# imu-adapter-e407.net
KiCad netlist of a schematic drawn in EAGLE
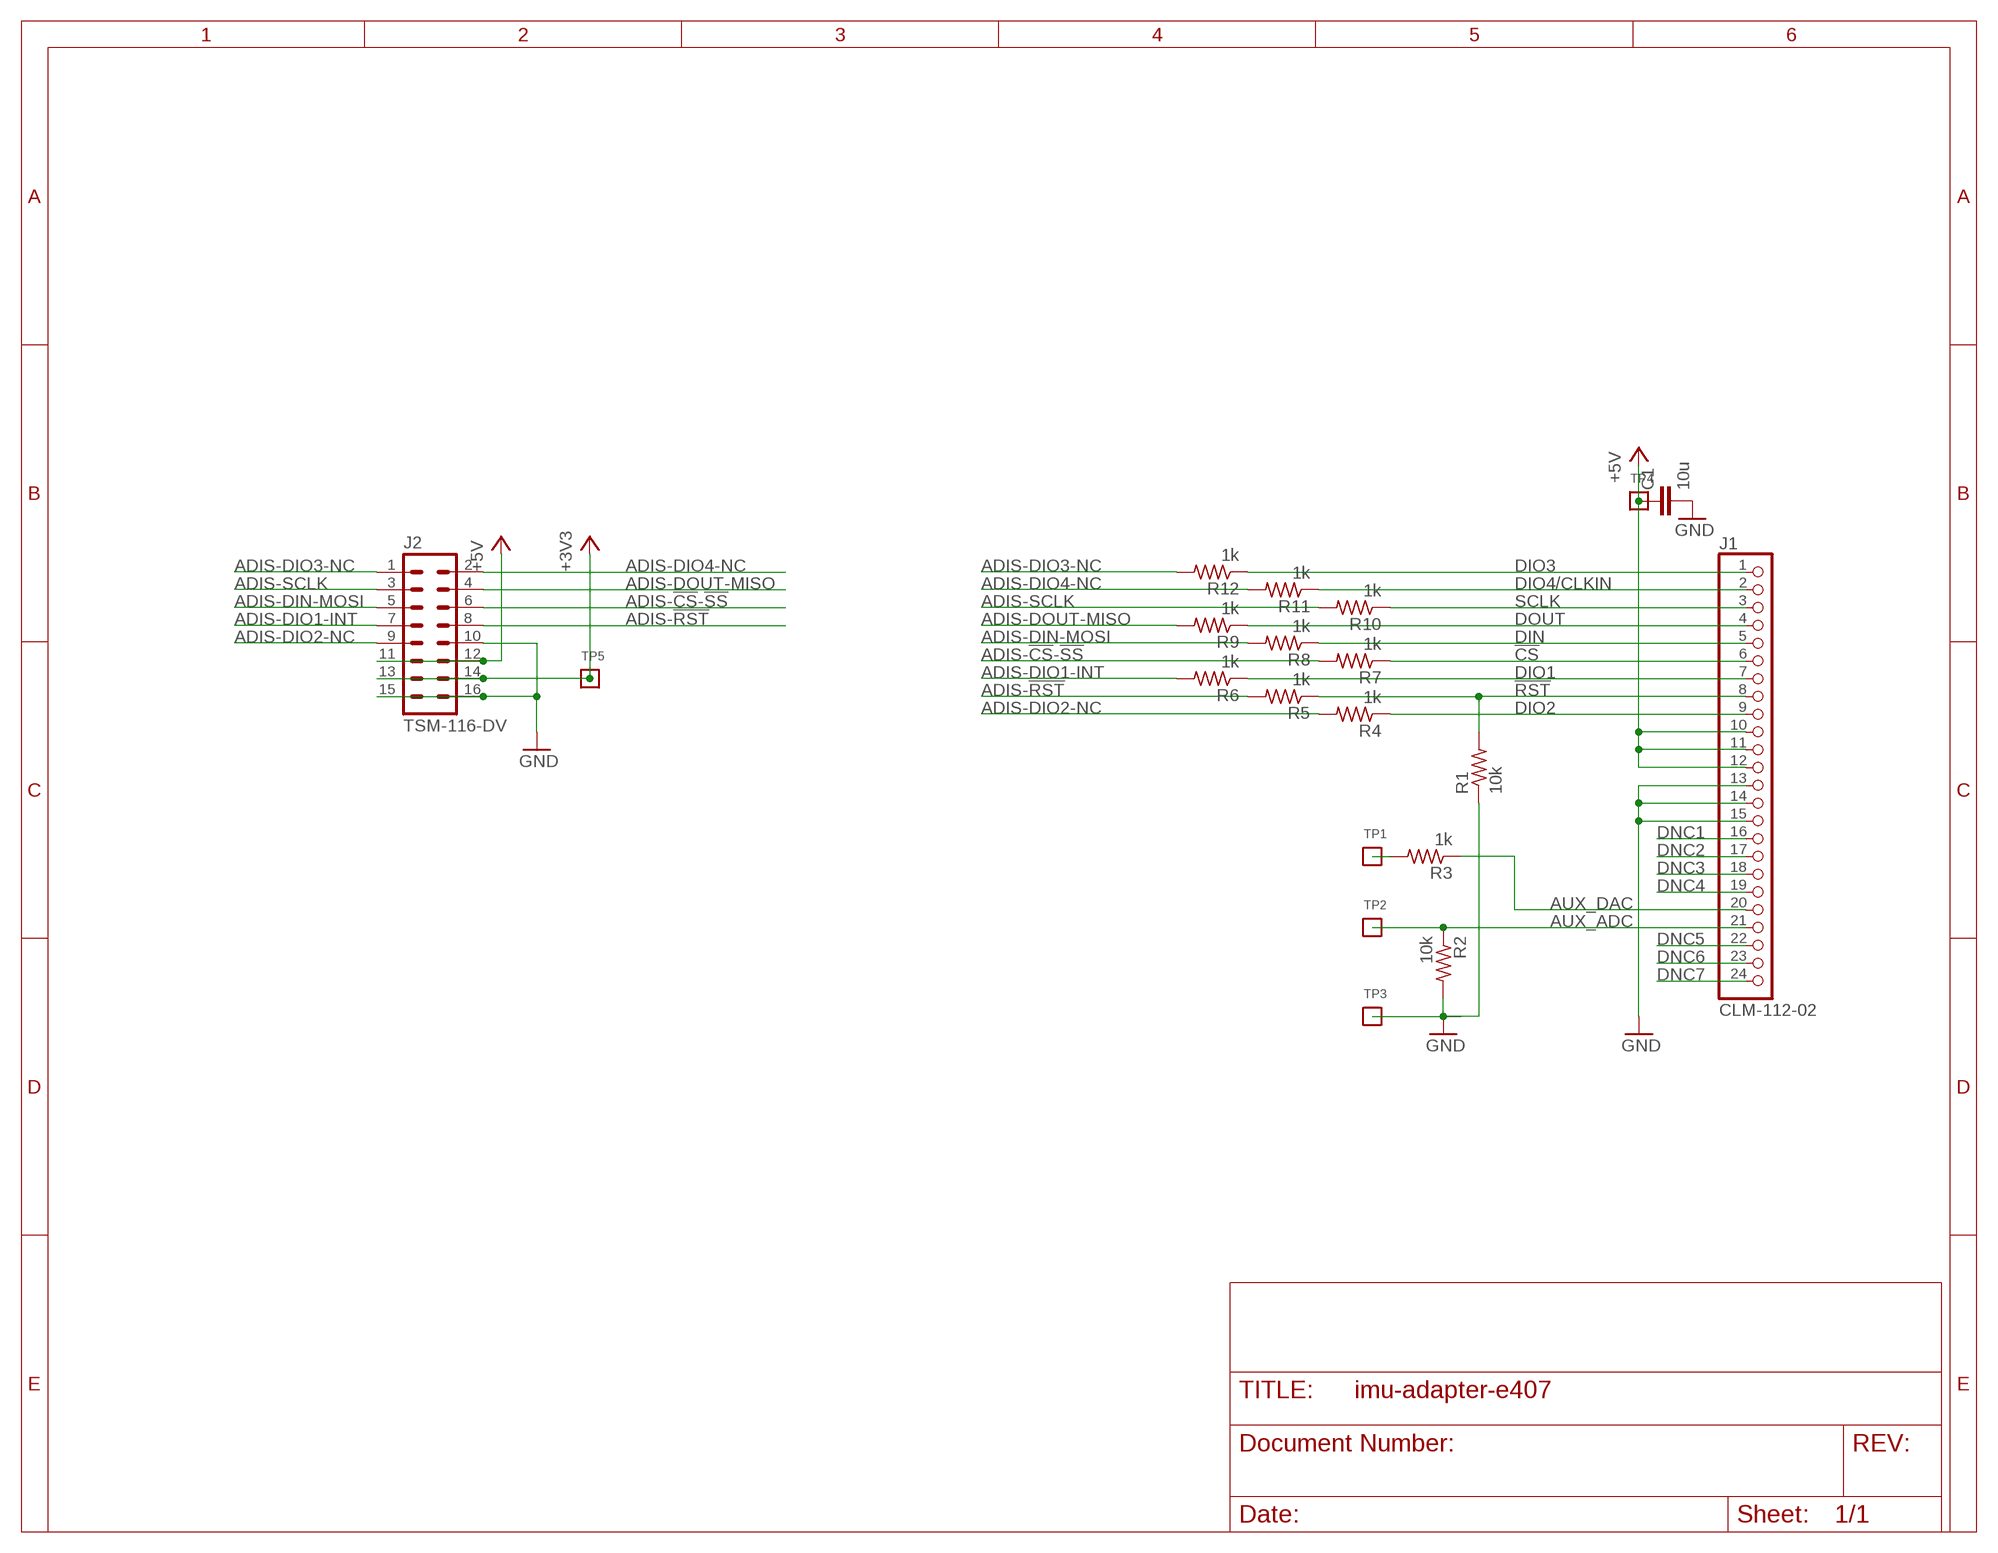
[diagram p0: schematic, sheet 1]

(export (version "E")
  (design (tool "Eeschema 10.0.6"))
  (components
    (comp (ref "C1")
      (value "10u")
      (footprint "eagle-import:0805-B-NOSILK")
      (libsource (lib "eagle-import") (part "C-EU0805-B-NOSILK"))
    )
    (comp (ref "J1")
      (value "CLM-112-02")
      (footprint "eagle-import:CLM-112-02-XX-D-A")
      (libsource (lib "eagle-import") (part "CLM-112-02"))
    )
    (comp (ref "J2")
      (value "TSM-116-DV")
      (footprint "eagle-import:TSM-116-DV")
      (libsource (lib "eagle-import") (part "TSM-116-DV"))
    )
    (comp (ref "R1")
      (value "10k")
      (footprint "eagle-import:0603-B-NOSILK")
      (libsource (lib "eagle-import") (part "R-US_0603-B-NOSILK"))
    )
    (comp (ref "R2")
      (value "10k")
      (footprint "eagle-import:0603-B-NOSILK")
      (libsource (lib "eagle-import") (part "R-US_0603-B-NOSILK"))
    )
    (comp (ref "R3")
      (value "1k")
      (footprint "eagle-import:0603-B-NOSILK")
      (libsource (lib "eagle-import") (part "R-US_0603-B-NOSILK"))
    )
    (comp (ref "R4")
      (value "1k")
      (footprint "eagle-import:0603-B-NOSILK")
      (libsource (lib "eagle-import") (part "R-US_0603-B-NOSILK"))
    )
    (comp (ref "R5")
      (value "1k")
      (footprint "eagle-import:0603-B-NOSILK")
      (libsource (lib "eagle-import") (part "R-US_0603-B-NOSILK"))
    )
    (comp (ref "R6")
      (value "1k")
      (footprint "eagle-import:0603-B-NOSILK")
      (libsource (lib "eagle-import") (part "R-US_0603-B-NOSILK"))
    )
    (comp (ref "R7")
      (value "1k")
      (footprint "eagle-import:0603-B-NOSILK")
      (libsource (lib "eagle-import") (part "R-US_0603-B-NOSILK"))
    )
    (comp (ref "R8")
      (value "1k")
      (footprint "eagle-import:0603-B-NOSILK")
      (libsource (lib "eagle-import") (part "R-US_0603-B-NOSILK"))
    )
    (comp (ref "R9")
      (value "1k")
      (footprint "eagle-import:0603-B-NOSILK")
      (libsource (lib "eagle-import") (part "R-US_0603-B-NOSILK"))
    )
    (comp (ref "R10")
      (value "1k")
      (footprint "eagle-import:0603-B-NOSILK")
      (libsource (lib "eagle-import") (part "R-US_0603-B-NOSILK"))
    )
    (comp (ref "R11")
      (value "1k")
      (footprint "eagle-import:0603-B-NOSILK")
      (libsource (lib "eagle-import") (part "R-US_0603-B-NOSILK"))
    )
    (comp (ref "R12")
      (value "1k")
      (footprint "eagle-import:0603-B-NOSILK")
      (libsource (lib "eagle-import") (part "R-US_0603-B-NOSILK"))
    )
    (comp (ref "TP1")
      (value "TEST-POINT")
      (footprint "eagle-import:2MM-TEST-POINT")
      (libsource (lib "eagle-import") (part "TEST-POINT"))
    )
    (comp (ref "TP2")
      (value "TEST-POINT")
      (footprint "eagle-import:2MM-TEST-POINT")
      (libsource (lib "eagle-import") (part "TEST-POINT"))
    )
    (comp (ref "TP3")
      (value "TEST-POINT")
      (footprint "eagle-import:2MM-TEST-POINT")
      (libsource (lib "eagle-import") (part "TEST-POINT"))
    )
    (comp (ref "TP4")
      (value "TEST-POINT")
      (footprint "eagle-import:2MM-TEST-POINT")
      (libsource (lib "eagle-import") (part "TEST-POINT"))
    )
    (comp (ref "TP5")
      (value "TEST-POINT")
      (footprint "eagle-import:2MM-TEST-POINT")
      (libsource (lib "eagle-import") (part "TEST-POINT"))
    )
  )
  (nets
    (net (code "1") (name "+3V3") (class "Default")
      (node (ref "J2") (pin "13") (pinfunction "13_13") (pintype "passive"))
      (node (ref "J2") (pin "14") (pinfunction "14_14") (pintype "passive"))
      (node (ref "TP5") (pin "1") (pinfunction "P$1_1") (pintype "passive"))
    )
    (net (code "2") (name "+5V") (class "Default")
      (node (ref "C1") (pin "1") (pinfunction "1_1") (pintype "passive"))
      (node (ref "J1") (pin "10") (pinfunction "10_10") (pintype "passive"))
      (node (ref "J1") (pin "11") (pinfunction "11_11") (pintype "passive"))
      (node (ref "J1") (pin "12") (pinfunction "12_12") (pintype "passive"))
      (node (ref "J2") (pin "11") (pinfunction "11_11") (pintype "passive"))
      (node (ref "J2") (pin "12") (pinfunction "12_12") (pintype "passive"))
      (node (ref "TP4") (pin "1") (pinfunction "P$1_1") (pintype "passive"))
    )
    (net (code "3") (name "/ADIS-DIN-MOSI") (class "Default")
      (node (ref "J2") (pin "5") (pinfunction "5_5") (pintype "passive"))
      (node (ref "R8") (pin "2") (pinfunction "2_2") (pintype "passive"))
    )
    (net (code "4") (name "/ADIS-DIO1-INT") (class "Default")
      (node (ref "J2") (pin "7") (pinfunction "7_7") (pintype "passive"))
      (node (ref "R6") (pin "2") (pinfunction "2_2") (pintype "passive"))
    )
    (net (code "5") (name "/ADIS-DIO2-NC") (class "Default")
      (node (ref "J2") (pin "9") (pinfunction "9_9") (pintype "passive"))
      (node (ref "R4") (pin "2") (pinfunction "2_2") (pintype "passive"))
    )
    (net (code "6") (name "/ADIS-DIO3-NC") (class "Default")
      (node (ref "J2") (pin "1") (pinfunction "1_1") (pintype "passive"))
      (node (ref "R12") (pin "2") (pinfunction "2_2") (pintype "passive"))
    )
    (net (code "7") (name "/ADIS-DIO4-NC") (class "Default")
      (node (ref "J2") (pin "2") (pinfunction "2_2") (pintype "passive"))
      (node (ref "R11") (pin "2") (pinfunction "2_2") (pintype "passive"))
    )
    (net (code "8") (name "/ADIS-DOUT-MISO") (class "Default")
      (node (ref "J2") (pin "4") (pinfunction "4_4") (pintype "passive"))
      (node (ref "R9") (pin "2") (pinfunction "2_2") (pintype "passive"))
    )
    (net (code "9") (name "/ADIS-SCLK") (class "Default")
      (node (ref "J2") (pin "3") (pinfunction "3_3") (pintype "passive"))
      (node (ref "R10") (pin "2") (pinfunction "2_2") (pintype "passive"))
    )
    (net (code "10") (name "/ADIS-~{CS}-~{SS}") (class "Default")
      (node (ref "J2") (pin "6") (pinfunction "6_6") (pintype "passive"))
      (node (ref "R7") (pin "2") (pinfunction "2_2") (pintype "passive"))
    )
    (net (code "11") (name "/ADIS-~{RST}") (class "Default")
      (node (ref "J2") (pin "8") (pinfunction "8_8") (pintype "passive"))
      (node (ref "R5") (pin "2") (pinfunction "2_2") (pintype "passive"))
    )
    (net (code "12") (name "/AUX_ADC") (class "Default")
      (node (ref "J1") (pin "21") (pinfunction "21_21") (pintype "passive"))
      (node (ref "R2") (pin "1") (pinfunction "1_1") (pintype "passive"))
      (node (ref "TP2") (pin "1") (pinfunction "P$1_1") (pintype "passive"))
    )
    (net (code "13") (name "/AUX_DAC") (class "Default")
      (node (ref "J1") (pin "20") (pinfunction "20_20") (pintype "passive"))
      (node (ref "R3") (pin "1") (pinfunction "1_1") (pintype "passive"))
    )
    (net (code "14") (name "/DIN") (class "Default")
      (node (ref "J1") (pin "5") (pinfunction "5_5") (pintype "passive"))
      (node (ref "R8") (pin "1") (pinfunction "1_1") (pintype "passive"))
    )
    (net (code "15") (name "/DIO1") (class "Default")
      (node (ref "J1") (pin "7") (pinfunction "7_7") (pintype "passive"))
      (node (ref "R6") (pin "1") (pinfunction "1_1") (pintype "passive"))
    )
    (net (code "16") (name "/DIO2") (class "Default")
      (node (ref "J1") (pin "9") (pinfunction "9_9") (pintype "passive"))
      (node (ref "R4") (pin "1") (pinfunction "1_1") (pintype "passive"))
    )
    (net (code "17") (name "/DIO3") (class "Default")
      (node (ref "J1") (pin "1") (pinfunction "1_1") (pintype "passive"))
      (node (ref "R12") (pin "1") (pinfunction "1_1") (pintype "passive"))
    )
    (net (code "18") (name "/DIO4{slash}CLKIN") (class "Default")
      (node (ref "J1") (pin "2") (pinfunction "2_2") (pintype "passive"))
      (node (ref "R11") (pin "1") (pinfunction "1_1") (pintype "passive"))
    )
    (net (code "19") (name "/DNC1") (class "Default")
      (node (ref "J1") (pin "16") (pinfunction "16_16") (pintype "passive"))
    )
    (net (code "20") (name "/DNC2") (class "Default")
      (node (ref "J1") (pin "17") (pinfunction "17_17") (pintype "passive"))
    )
    (net (code "21") (name "/DNC3") (class "Default")
      (node (ref "J1") (pin "18") (pinfunction "18_18") (pintype "passive"))
    )
    (net (code "22") (name "/DNC4") (class "Default")
      (node (ref "J1") (pin "19") (pinfunction "19_19") (pintype "passive"))
    )
    (net (code "23") (name "/DNC5") (class "Default")
      (node (ref "J1") (pin "22") (pinfunction "22_22") (pintype "passive"))
    )
    (net (code "24") (name "/DNC6") (class "Default")
      (node (ref "J1") (pin "23") (pinfunction "23_23") (pintype "passive"))
    )
    (net (code "25") (name "/DNC7") (class "Default")
      (node (ref "J1") (pin "24") (pinfunction "24_24") (pintype "passive"))
    )
    (net (code "26") (name "/DOUT") (class "Default")
      (node (ref "J1") (pin "4") (pinfunction "4_4") (pintype "passive"))
      (node (ref "R9") (pin "1") (pinfunction "1_1") (pintype "passive"))
    )
    (net (code "27") (name "/SCLK") (class "Default")
      (node (ref "J1") (pin "3") (pinfunction "3_3") (pintype "passive"))
      (node (ref "R10") (pin "1") (pinfunction "1_1") (pintype "passive"))
    )
    (net (code "28") (name "/~{CS}") (class "Default")
      (node (ref "J1") (pin "6") (pinfunction "6_6") (pintype "passive"))
      (node (ref "R7") (pin "1") (pinfunction "1_1") (pintype "passive"))
    )
    (net (code "29") (name "/~{RST}") (class "Default")
      (node (ref "J1") (pin "8") (pinfunction "8_8") (pintype "passive"))
      (node (ref "R1") (pin "2") (pinfunction "2_2") (pintype "passive"))
      (node (ref "R5") (pin "1") (pinfunction "1_1") (pintype "passive"))
    )
    (net (code "30") (name "GND") (class "Default")
      (node (ref "C1") (pin "2") (pinfunction "2_2") (pintype "passive"))
      (node (ref "J1") (pin "13") (pinfunction "13_13") (pintype "passive"))
      (node (ref "J1") (pin "14") (pinfunction "14_14") (pintype "passive"))
      (node (ref "J1") (pin "15") (pinfunction "15_15") (pintype "passive"))
      (node (ref "J2") (pin "10") (pinfunction "10_10") (pintype "passive"))
      (node (ref "J2") (pin "15") (pinfunction "15_15") (pintype "passive"))
      (node (ref "J2") (pin "16") (pinfunction "16_16") (pintype "passive"))
      (node (ref "R1") (pin "1") (pinfunction "1_1") (pintype "passive"))
      (node (ref "R2") (pin "2") (pinfunction "2_2") (pintype "passive"))
      (node (ref "TP3") (pin "1") (pinfunction "P$1_1") (pintype "passive"))
    )
    (net (code "31") (name "Net-(TP1-P$1)") (class "Default")
      (node (ref "R3") (pin "2") (pinfunction "2_2") (pintype "passive"))
      (node (ref "TP1") (pin "1") (pinfunction "P$1_1") (pintype "passive"))
    )
  )
)
